# shoes.net
KiCad netlist of a schematic drawn in EAGLE
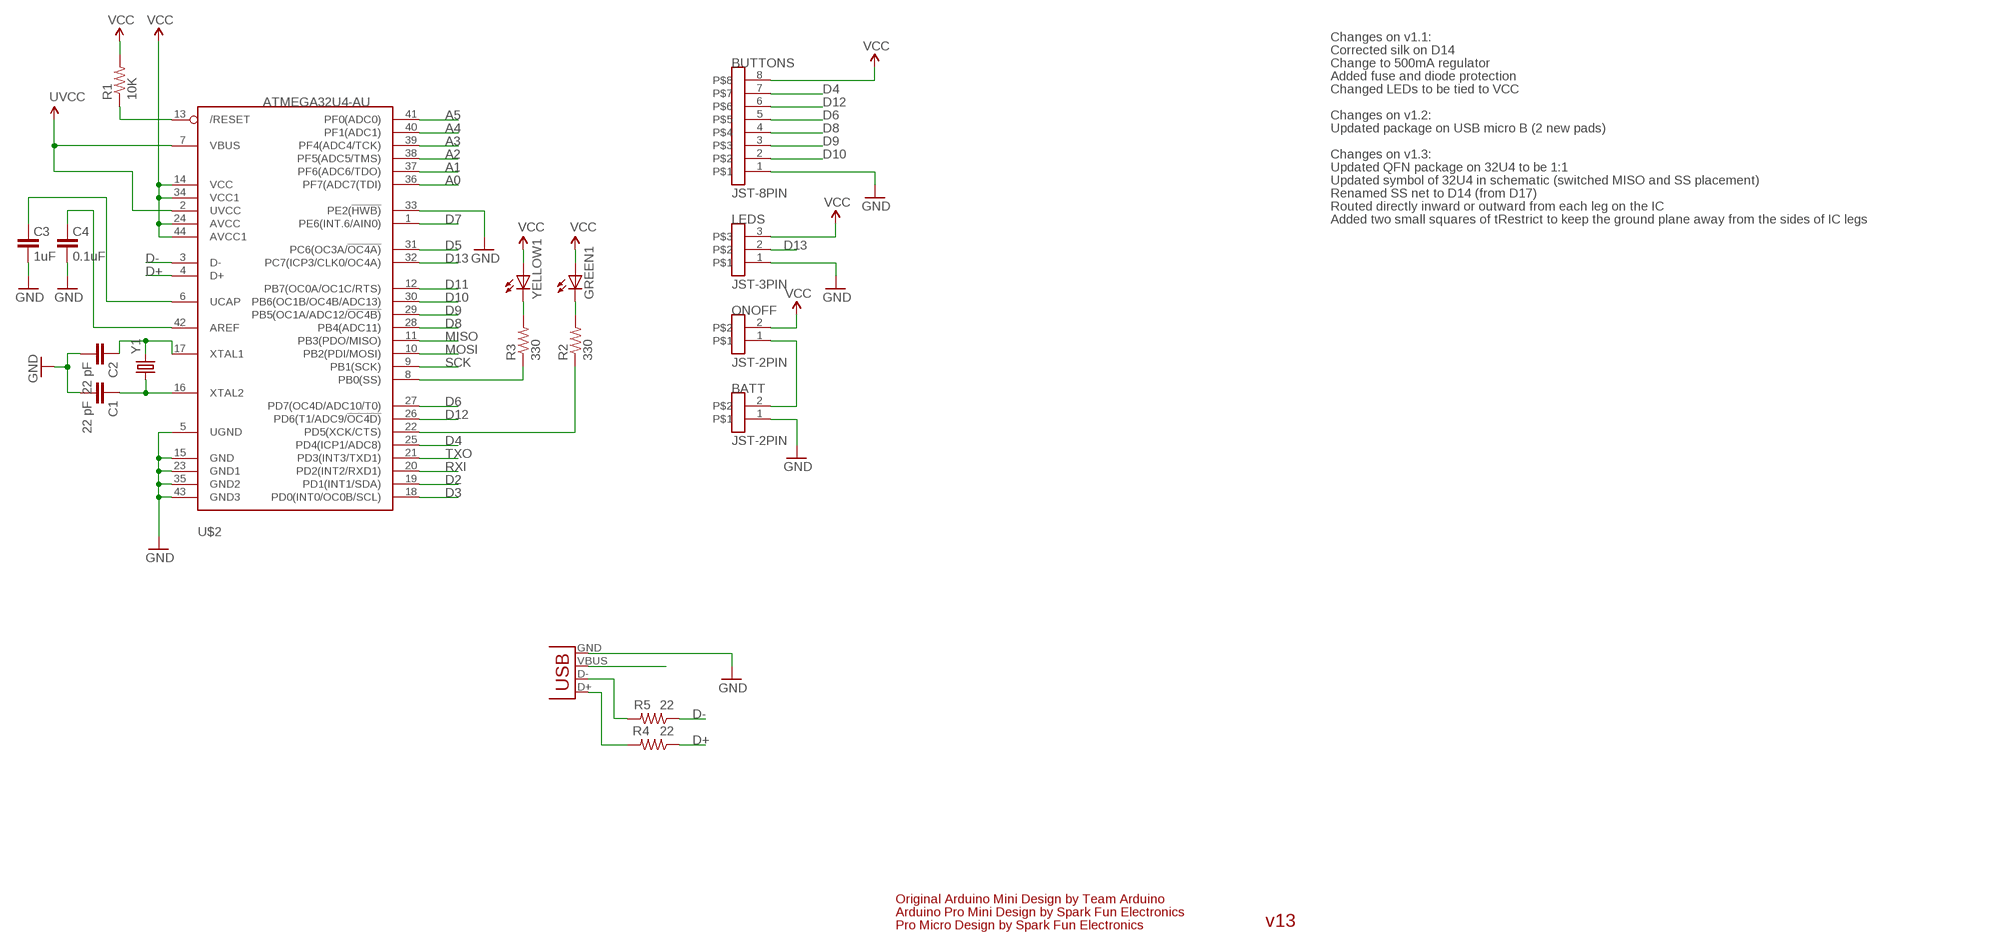
[diagram p0: schematic, sheet 1]

(export (version "E")
  (design (tool "Eeschema 10.0.6"))
  (components
    (comp (ref "BATT")
      (value "JST-2PIN")
      (footprint "eagle-import:JST-PH-2")
      (libsource (lib "eagle-import") (part "JST-2PIN"))
    )
    (comp (ref "BUTTONS")
      (value "JST-8PIN")
      (footprint "eagle-import:JST-PH-8")
      (libsource (lib "eagle-import") (part "JST-8PIN"))
    )
    (comp (ref "C1")
      (value "22 pF")
      (footprint "eagle-import:0805")
      (libsource (lib "eagle-import") (part "CAP0805"))
    )
    (comp (ref "C2")
      (value "22 pF")
      (footprint "eagle-import:0805")
      (libsource (lib "eagle-import") (part "CAP0805"))
    )
    (comp (ref "C3")
      (value "1uF")
      (footprint "eagle-import:0805")
      (libsource (lib "eagle-import") (part "SparkFun_CAP0805"))
    )
    (comp (ref "C4")
      (value "0.1uF")
      (footprint "eagle-import:0805")
      (libsource (lib "eagle-import") (part "SparkFun_CAP0805"))
    )
    (comp (ref "GREEN1")
      (value "LED")
      (footprint "eagle-import:0805_P")
      (libsource (lib "eagle-import") (part "LED"))
    )
    (comp (ref "LEDS")
      (value "JST-3PIN")
      (footprint "eagle-import:JST-PH-3")
      (libsource (lib "eagle-import") (part "JST-3PIN"))
    )
    (comp (ref "ONOFF")
      (value "JST-2PIN")
      (footprint "eagle-import:JST-PH-2")
      (libsource (lib "eagle-import") (part "JST-2PIN"))
    )
    (comp (ref "R1")
      (value "10K")
      (footprint "eagle-import:0805")
      (libsource (lib "eagle-import") (part "RESISTOR0805-RES"))
    )
    (comp (ref "R2")
      (value "330")
      (footprint "eagle-import:0805")
      (libsource (lib "eagle-import") (part "RESISTOR0805-RES"))
    )
    (comp (ref "R3")
      (value "330")
      (footprint "eagle-import:0805")
      (libsource (lib "eagle-import") (part "RESISTOR0805-RES"))
    )
    (comp (ref "R4")
      (value "22")
      (footprint "eagle-import:0805")
      (libsource (lib "eagle-import") (part "RESISTOR0805-RES"))
    )
    (comp (ref "R5")
      (value "22")
      (footprint "eagle-import:0805")
      (libsource (lib "eagle-import") (part "RESISTOR0805-RES"))
    )
    (comp (ref "U$2")
      (value "ATMEGA32U4-AU")
      (footprint "eagle-import:TQFP44")
      (libsource (lib "eagle-import") (part "ATMEGA32U4-AU"))
    )
    (comp (ref "X2")
      (value "USB-MICROB")
      (footprint "eagle-import:USB-MICROB")
      (libsource (lib "eagle-import") (part "USB-MICROB"))
    )
    (comp (ref "Y1")
      (value "CRYSTALHC49US")
      (footprint "eagle-import:HC49US")
      (libsource (lib "eagle-import") (part "CRYSTALHC49US"))
    )
    (comp (ref "YELLOW1")
      (value "LED")
      (footprint "eagle-import:0805_P")
      (libsource (lib "eagle-import") (part "LED"))
    )
  )
  (nets
    (net (code "1") (name "/A0") (class "Default")
      (node (ref "U$2") (pin "36") (pinfunction "PF7(ADC7(TDI)_36") (pintype "bidirectional"))
    )
    (net (code "2") (name "/A1") (class "Default")
      (node (ref "U$2") (pin "37") (pinfunction "PF6(ADC6/TDO)_37") (pintype "bidirectional"))
    )
    (net (code "3") (name "/A2") (class "Default")
      (node (ref "U$2") (pin "38") (pinfunction "PF5(ADC5/TMS)_38") (pintype "bidirectional"))
    )
    (net (code "4") (name "/A3") (class "Default")
      (node (ref "U$2") (pin "39") (pinfunction "PF4(ADC4/TCK)_39") (pintype "bidirectional"))
    )
    (net (code "5") (name "/A4") (class "Default")
      (node (ref "U$2") (pin "40") (pinfunction "PF1(ADC1)_40") (pintype "bidirectional"))
    )
    (net (code "6") (name "/A5") (class "Default")
      (node (ref "U$2") (pin "41") (pinfunction "PF0(ADC0)_41") (pintype "bidirectional"))
    )
    (net (code "7") (name "/D+") (class "Default")
      (node (ref "R4") (pin "1") (pinfunction "1_1") (pintype "passive"))
      (node (ref "U$2") (pin "4") (pinfunction "D+_4") (pintype "bidirectional"))
    )
    (net (code "8") (name "/D-") (class "Default")
      (node (ref "R5") (pin "1") (pinfunction "1_1") (pintype "passive"))
      (node (ref "U$2") (pin "3") (pinfunction "D-_3") (pintype "bidirectional"))
    )
    (net (code "9") (name "/D2") (class "Default")
      (node (ref "U$2") (pin "19") (pinfunction "PD1(INT1/SDA)_19") (pintype "bidirectional"))
    )
    (net (code "10") (name "/D3") (class "Default")
      (node (ref "U$2") (pin "18") (pinfunction "PD0(INT0/OC0B/SCL)_18") (pintype "bidirectional"))
    )
    (net (code "11") (name "/D4") (class "Default")
      (node (ref "BUTTONS") (pin "7") (pinfunction "P$7_7") (pintype "bidirectional"))
      (node (ref "U$2") (pin "25") (pinfunction "PD4(ICP1/ADC8)_25") (pintype "bidirectional"))
    )
    (net (code "12") (name "/D5") (class "Default")
      (node (ref "U$2") (pin "31") (pinfunction "PC6(OC3A/~{OC4A})_31") (pintype "bidirectional"))
    )
    (net (code "13") (name "/D6") (class "Default")
      (node (ref "BUTTONS") (pin "5") (pinfunction "P$5_5") (pintype "bidirectional"))
      (node (ref "U$2") (pin "27") (pinfunction "PD7(OC4D/ADC10/T0)_27") (pintype "bidirectional"))
    )
    (net (code "14") (name "/D7") (class "Default")
      (node (ref "U$2") (pin "1") (pinfunction "PE6(INT.6/AIN0)_1") (pintype "bidirectional"))
    )
    (net (code "15") (name "/D8") (class "Default")
      (node (ref "BUTTONS") (pin "4") (pinfunction "P$4_4") (pintype "bidirectional"))
      (node (ref "U$2") (pin "28") (pinfunction "PB4(ADC11)_28") (pintype "bidirectional"))
    )
    (net (code "16") (name "/D9") (class "Default")
      (node (ref "BUTTONS") (pin "3") (pinfunction "P$3_3") (pintype "bidirectional"))
      (node (ref "U$2") (pin "29") (pinfunction "PB5(OC1A/ADC12/~{OC4B})_29") (pintype "bidirectional"))
    )
    (net (code "17") (name "/D10") (class "Default")
      (node (ref "BUTTONS") (pin "2") (pinfunction "P$2_2") (pintype "bidirectional"))
      (node (ref "U$2") (pin "30") (pinfunction "PB6(OC1B/OC4B/ADC13)_30") (pintype "bidirectional"))
    )
    (net (code "18") (name "/D11") (class "Default")
      (node (ref "U$2") (pin "12") (pinfunction "PB7(OC0A/OC1C/RTS)_12") (pintype "bidirectional"))
    )
    (net (code "19") (name "/D12") (class "Default")
      (node (ref "BUTTONS") (pin "6") (pinfunction "P$6_6") (pintype "bidirectional"))
      (node (ref "U$2") (pin "26") (pinfunction "PD6(T1/ADC9/~{OC4D})_26") (pintype "bidirectional"))
    )
    (net (code "20") (name "/D13") (class "Default")
      (node (ref "LEDS") (pin "2") (pinfunction "P$2_2") (pintype "bidirectional"))
      (node (ref "U$2") (pin "32") (pinfunction "PC7(ICP3/CLK0/OC4A)_32") (pintype "bidirectional"))
    )
    (net (code "21") (name "/MISO") (class "Default")
      (node (ref "U$2") (pin "11") (pinfunction "PB3(PDO/MISO)_11") (pintype "bidirectional"))
    )
    (net (code "22") (name "/MOSI") (class "Default")
      (node (ref "U$2") (pin "10") (pinfunction "PB2(PDI/MOSI)_10") (pintype "bidirectional"))
    )
    (net (code "23") (name "/RXI") (class "Default")
      (node (ref "U$2") (pin "20") (pinfunction "PD2(INT2/RXD1)_20") (pintype "bidirectional"))
    )
    (net (code "24") (name "/SCK") (class "Default")
      (node (ref "U$2") (pin "9") (pinfunction "PB1(SCK)_9") (pintype "bidirectional"))
    )
    (net (code "25") (name "/TXO") (class "Default")
      (node (ref "U$2") (pin "21") (pinfunction "PD3(INT3/TXD1)_21") (pintype "bidirectional"))
    )
    (net (code "26") (name "GND") (class "Default")
      (node (ref "BATT") (pin "1") (pinfunction "P$1_1") (pintype "bidirectional"))
      (node (ref "BUTTONS") (pin "1") (pinfunction "P$1_1") (pintype "bidirectional"))
      (node (ref "C1") (pin "POS") (pinfunction "2_POS") (pintype "passive"))
      (node (ref "C2") (pin "POS") (pinfunction "2_POS") (pintype "passive"))
      (node (ref "C3") (pin "1") (pinfunction "1_1") (pintype "passive"))
      (node (ref "C4") (pin "1") (pinfunction "1_1") (pintype "passive"))
      (node (ref "LEDS") (pin "1") (pinfunction "P$1_1") (pintype "bidirectional"))
      (node (ref "U$2") (pin "15") (pinfunction "GND_15") (pintype "bidirectional"))
      (node (ref "U$2") (pin "23") (pinfunction "GND1_23") (pintype "bidirectional"))
      (node (ref "U$2") (pin "33") (pinfunction "PE2(~{HWB})_33") (pintype "bidirectional"))
      (node (ref "U$2") (pin "35") (pinfunction "GND2_35") (pintype "bidirectional"))
      (node (ref "U$2") (pin "43") (pinfunction "GND3_43") (pintype "bidirectional"))
      (node (ref "U$2") (pin "5") (pinfunction "UGND_5") (pintype "bidirectional"))
      (node (ref "X2") (pin "GND") (pinfunction "GND_GND") (pintype "bidirectional"))
    )
    (net (code "27") (name "Net-(BATT-P$2)") (class "Default")
      (node (ref "BATT") (pin "2") (pinfunction "P$2_2") (pintype "bidirectional"))
      (node (ref "ONOFF") (pin "1") (pinfunction "P$1_1") (pintype "bidirectional"))
    )
    (net (code "28") (name "Net-(C1-1)") (class "Default")
      (node (ref "C1") (pin "NEG") (pinfunction "1_NEG") (pintype "passive"))
      (node (ref "U$2") (pin "16") (pinfunction "XTAL2_16") (pintype "bidirectional"))
      (node (ref "Y1") (pin "1") (pinfunction "1_1") (pintype "passive"))
    )
    (net (code "29") (name "Net-(C2-1)") (class "Default")
      (node (ref "C2") (pin "NEG") (pinfunction "1_NEG") (pintype "passive"))
      (node (ref "U$2") (pin "17") (pinfunction "XTAL1_17") (pintype "bidirectional"))
      (node (ref "Y1") (pin "2") (pinfunction "2_2") (pintype "passive"))
    )
    (net (code "30") (name "Net-(GREEN1-C)") (class "Default")
      (node (ref "GREEN1") (pin "POS") (pinfunction "C_POS") (pintype "passive"))
      (node (ref "R2") (pin "2") (pinfunction "2_2") (pintype "passive"))
    )
    (net (code "31") (name "Net-(R4-Pad2)") (class "Default")
      (node (ref "R4") (pin "2") (pinfunction "2_2") (pintype "passive"))
      (node (ref "X2") (pin "D+") (pinfunction "D+_D+") (pintype "bidirectional"))
    )
    (net (code "32") (name "Net-(R5-Pad2)") (class "Default")
      (node (ref "R5") (pin "2") (pinfunction "2_2") (pintype "passive"))
      (node (ref "X2") (pin "D-") (pinfunction "D-_D-") (pintype "bidirectional"))
    )
    (net (code "33") (name "Net-(U$2-AREF)") (class "Default")
      (node (ref "C4") (pin "2") (pinfunction "2_2") (pintype "passive"))
      (node (ref "U$2") (pin "42") (pinfunction "AREF_42") (pintype "bidirectional"))
    )
    (net (code "34") (name "Net-(U$2-PB0(SS))") (class "Default")
      (node (ref "R3") (pin "1") (pinfunction "1_1") (pintype "passive"))
      (node (ref "U$2") (pin "8") (pinfunction "PB0(SS)_8") (pintype "bidirectional"))
    )
    (net (code "35") (name "Net-(U$2-PD5(XCK{slash}CTS))") (class "Default")
      (node (ref "R2") (pin "1") (pinfunction "1_1") (pintype "passive"))
      (node (ref "U$2") (pin "22") (pinfunction "PD5(XCK/CTS)_22") (pintype "bidirectional"))
    )
    (net (code "36") (name "Net-(U$2-UCAP)") (class "Default")
      (node (ref "C3") (pin "2") (pinfunction "2_2") (pintype "passive"))
      (node (ref "U$2") (pin "6") (pinfunction "UCAP_6") (pintype "bidirectional"))
    )
    (net (code "37") (name "Net-(U$2-{slash}RESET)") (class "Default")
      (node (ref "R1") (pin "1") (pinfunction "1_1") (pintype "passive"))
      (node (ref "U$2") (pin "13") (pinfunction "/RESET_13") (pintype "bidirectional"))
    )
    (net (code "38") (name "Net-(YELLOW1-C)") (class "Default")
      (node (ref "R3") (pin "2") (pinfunction "2_2") (pintype "passive"))
      (node (ref "YELLOW1") (pin "POS") (pinfunction "C_POS") (pintype "passive"))
    )
    (net (code "39") (name "UVCC") (class "Default")
      (node (ref "U$2") (pin "2") (pinfunction "UVCC_2") (pintype "bidirectional"))
      (node (ref "U$2") (pin "7") (pinfunction "VBUS_7") (pintype "bidirectional"))
      (node (ref "X2") (pin "VBUS") (pinfunction "VBUS_VBUS") (pintype "bidirectional"))
    )
    (net (code "40") (name "VCC") (class "Default")
      (node (ref "BUTTONS") (pin "8") (pinfunction "P$8_8") (pintype "bidirectional"))
      (node (ref "GREEN1") (pin "NEG") (pinfunction "A_NEG") (pintype "passive"))
      (node (ref "LEDS") (pin "3") (pinfunction "P$3_3") (pintype "bidirectional"))
      (node (ref "ONOFF") (pin "2") (pinfunction "P$2_2") (pintype "bidirectional"))
      (node (ref "R1") (pin "2") (pinfunction "2_2") (pintype "passive"))
      (node (ref "U$2") (pin "14") (pinfunction "VCC_14") (pintype "bidirectional"))
      (node (ref "U$2") (pin "24") (pinfunction "AVCC_24") (pintype "bidirectional"))
      (node (ref "U$2") (pin "34") (pinfunction "VCC1_34") (pintype "bidirectional"))
      (node (ref "U$2") (pin "44") (pinfunction "AVCC1_44") (pintype "bidirectional"))
      (node (ref "YELLOW1") (pin "NEG") (pinfunction "A_NEG") (pintype "passive"))
    )
  )
)
